# untitled.net
KiCad netlist of a schematic drawn in EAGLE
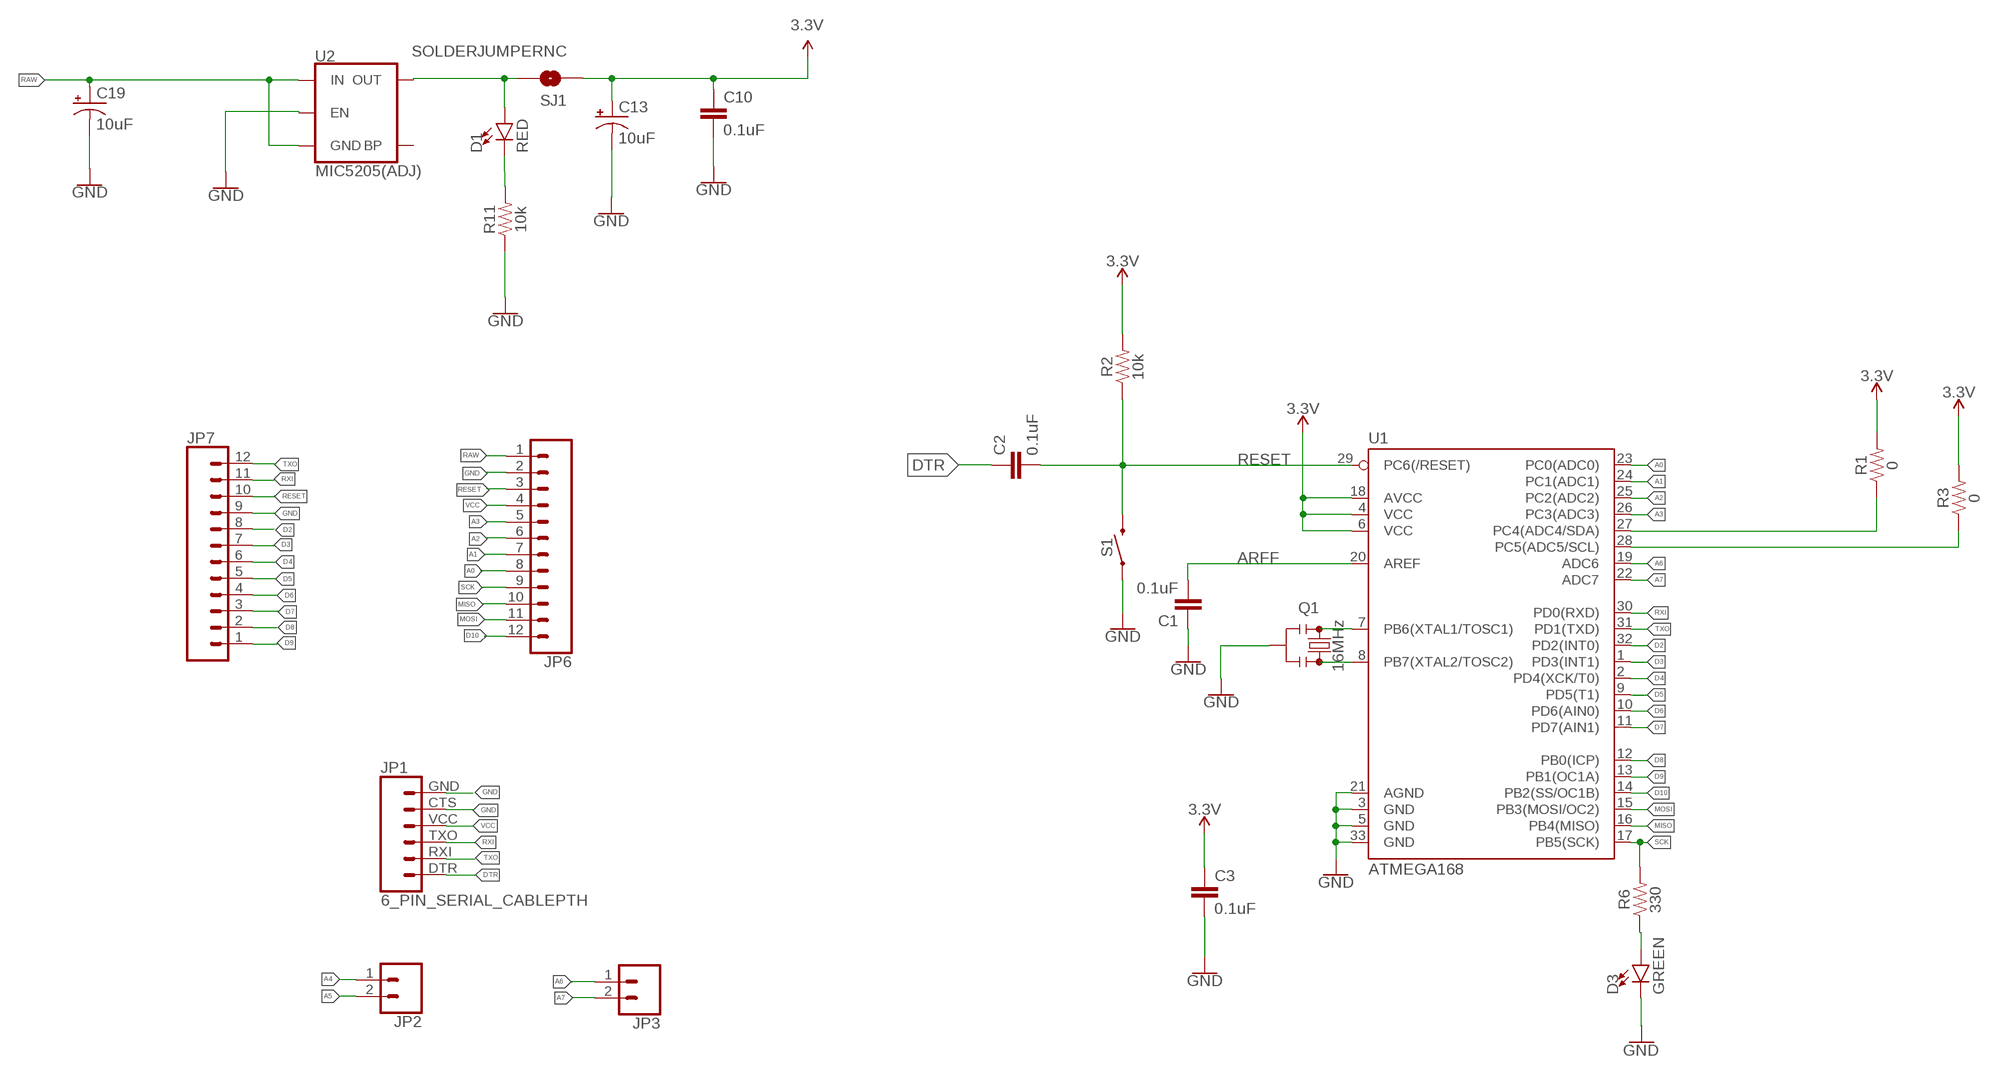
[diagram p0: schematic, sheet 1]

(export (version "E")
  (design (tool "Eeschema 10.0.6"))
  (components
    (comp (ref "C1")
      (value "0.1uF")
      (footprint "eagle-import:0603")
      (libsource (lib "eagle-import") (part "0.1UF-0603-25V-(+80/-20%)"))
    )
    (comp (ref "C2")
      (value "0.1uF")
      (footprint "eagle-import:0603")
      (libsource (lib "eagle-import") (part "0.1UF-0603-25V-(+80/-20%)"))
    )
    (comp (ref "C3")
      (value "0.1uF")
      (footprint "eagle-import:0603")
      (libsource (lib "eagle-import") (part "0.1UF-0603-25V-(+80/-20%)"))
    )
    (comp (ref "C10")
      (value "0.1uF")
      (footprint "eagle-import:0603")
      (libsource (lib "eagle-import") (part "0.1UF-0603-25V-(+80/-20%)"))
    )
    (comp (ref "C13")
      (value "10uF")
      (footprint "eagle-import:0603-POLAR")
      (libsource (lib "eagle-import") (part "10UF-POLAR-0603-6.3V-20%(TANT)"))
    )
    (comp (ref "C19")
      (value "10uF")
      (footprint "eagle-import:0603-POLAR")
      (libsource (lib "eagle-import") (part "10UF-POLAR-0603-6.3V-20%(TANT)"))
    )
    (comp (ref "D1")
      (value "RED")
      (footprint "eagle-import:LED-0603")
      (libsource (lib "eagle-import") (part "LED-RED0603"))
    )
    (comp (ref "D3")
      (value "GREEN")
      (footprint "eagle-import:LED-0603")
      (libsource (lib "eagle-import") (part "LED-GREEN0603"))
    )
    (comp (ref "JP1")
      (value "6_PIN_SERIAL_CABLEPTH")
      (footprint "eagle-import:FTDI_BASIC")
      (libsource (lib "eagle-import") (part "6_PIN_SERIAL_CABLEPTH"))
    )
    (comp (ref "JP2")
      (value "CONN_02")
      (footprint "eagle-import:1X02")
      (libsource (lib "eagle-import") (part "CONN_02"))
    )
    (comp (ref "JP3")
      (value "CONN_02")
      (footprint "eagle-import:1X02")
      (libsource (lib "eagle-import") (part "CONN_02"))
    )
    (comp (ref "JP6")
      (value "CONN_12")
      (footprint "eagle-import:1X12")
      (libsource (lib "eagle-import") (part "CONN_12"))
    )
    (comp (ref "JP7")
      (value "CONN_12")
      (footprint "eagle-import:1X12")
      (libsource (lib "eagle-import") (part "CONN_12"))
    )
    (comp (ref "Q1")
      (value "16MHz")
      (footprint "eagle-import:RESONATOR-SMD-3.2X1.3")
      (libsource (lib "eagle-import") (part "RESONATOR-16MHZSMD_3.2X1.3"))
    )
    (comp (ref "R1")
      (value "0")
      (footprint "eagle-import:0603")
      (libsource (lib "eagle-import") (part "0OHM-0603-1/10W"))
    )
    (comp (ref "R2")
      (value "10k")
      (footprint "eagle-import:0603")
      (libsource (lib "eagle-import") (part "10KOHM-0603-1/10W-1%"))
    )
    (comp (ref "R3")
      (value "0")
      (footprint "eagle-import:0603")
      (libsource (lib "eagle-import") (part "0OHM-0603-1/10W"))
    )
    (comp (ref "R6")
      (value "330")
      (footprint "eagle-import:0603")
      (libsource (lib "eagle-import") (part "330OHM-0603-1/10W-1%"))
    )
    (comp (ref "R11")
      (value "10k")
      (footprint "eagle-import:0603")
      (libsource (lib "eagle-import") (part "10KOHM-0603-1/10W-1%"))
    )
    (comp (ref "S1")
      (value "MOMENTARY-SWITCH-SPST-SMD-5.2-TALL-REDUNDANT")
      (footprint "eagle-import:TACTILE_SWITCH_SMD_5.2MM")
      (libsource (lib "eagle-import") (part "MOMENTARY-SWITCH-SPST-SMD-5.2-TALL-REDUNDANT"))
    )
    (comp (ref "SJ1")
      (value "SOLDERJUMPERNC")
      (footprint "eagle-import:SJ_2S")
      (libsource (lib "eagle-import") (part "SOLDERJUMPERNC"))
    )
    (comp (ref "U1")
      (value "ATMEGA168")
      (footprint "eagle-import:MLF32")
      (libsource (lib "eagle-import") (part "ATMEGA168_MLFMLF"))
    )
    (comp (ref "U2")
      (value "MIC5205(ADJ)")
      (footprint "eagle-import:SOT23-5")
      (libsource (lib "eagle-import") (part "V_REG_MIC5205ADJ"))
    )
  )
  (nets
    (net (code "1") (name "/ARFF") (class "Default")
      (node (ref "C1") (pin "2") (pinfunction "2_2") (pintype "passive"))
      (node (ref "U1") (pin "20") (pinfunction "AREF_20") (pintype "bidirectional"))
    )
    (net (code "2") (name "3.3V") (class "Default")
      (node (ref "C10") (pin "1") (pinfunction "1_1") (pintype "passive"))
      (node (ref "C13") (pin "+") (pinfunction "+_+") (pintype "passive"))
      (node (ref "C3") (pin "1") (pinfunction "1_1") (pintype "passive"))
      (node (ref "R1") (pin "2") (pinfunction "2_2") (pintype "passive"))
      (node (ref "R2") (pin "2") (pinfunction "2_2") (pintype "passive"))
      (node (ref "R3") (pin "2") (pinfunction "2_2") (pintype "passive"))
      (node (ref "SJ1") (pin "1") (pinfunction "1_1") (pintype "passive"))
      (node (ref "U1") (pin "18") (pinfunction "AVCC_18") (pintype "bidirectional"))
      (node (ref "U1") (pin "4") (pinfunction "VCC_4") (pintype "bidirectional"))
      (node (ref "U1") (pin "6") (pinfunction "VCC_6") (pintype "bidirectional"))
    )
    (net (code "3") (name "A0") (class "Default")
      (node (ref "JP6") (pin "8") (pinfunction "8_8") (pintype "passive"))
      (node (ref "U1") (pin "23") (pinfunction "PC0(ADC0)_23") (pintype "bidirectional"))
    )
    (net (code "4") (name "A1") (class "Default")
      (node (ref "JP6") (pin "7") (pinfunction "7_7") (pintype "passive"))
      (node (ref "U1") (pin "24") (pinfunction "PC1(ADC1)_24") (pintype "bidirectional"))
    )
    (net (code "5") (name "A2") (class "Default")
      (node (ref "JP6") (pin "6") (pinfunction "6_6") (pintype "passive"))
      (node (ref "U1") (pin "25") (pinfunction "PC2(ADC2)_25") (pintype "bidirectional"))
    )
    (net (code "6") (name "A3") (class "Default")
      (node (ref "JP6") (pin "5") (pinfunction "5_5") (pintype "passive"))
      (node (ref "U1") (pin "26") (pinfunction "PC3(ADC3)_26") (pintype "bidirectional"))
    )
    (net (code "7") (name "A4") (class "Default")
      (node (ref "JP2") (pin "1") (pinfunction "1_1") (pintype "passive"))
    )
    (net (code "8") (name "A5") (class "Default")
      (node (ref "JP2") (pin "2") (pinfunction "2_2") (pintype "passive"))
    )
    (net (code "9") (name "A6") (class "Default")
      (node (ref "JP3") (pin "1") (pinfunction "1_1") (pintype "passive"))
      (node (ref "U1") (pin "19") (pinfunction "ADC6_19") (pintype "bidirectional"))
    )
    (net (code "10") (name "A7") (class "Default")
      (node (ref "JP3") (pin "2") (pinfunction "2_2") (pintype "passive"))
      (node (ref "U1") (pin "22") (pinfunction "ADC7_22") (pintype "bidirectional"))
    )
    (net (code "11") (name "D2") (class "Default")
      (node (ref "JP7") (pin "8") (pinfunction "8_8") (pintype "passive"))
      (node (ref "U1") (pin "32") (pinfunction "PD2(INT0)_32") (pintype "bidirectional"))
    )
    (net (code "12") (name "D3") (class "Default")
      (node (ref "JP7") (pin "7") (pinfunction "7_7") (pintype "passive"))
      (node (ref "U1") (pin "1") (pinfunction "PD3(INT1)_1") (pintype "bidirectional"))
    )
    (net (code "13") (name "D4") (class "Default")
      (node (ref "JP7") (pin "6") (pinfunction "6_6") (pintype "passive"))
      (node (ref "U1") (pin "2") (pinfunction "PD4(XCK/T0)_2") (pintype "bidirectional"))
    )
    (net (code "14") (name "D5") (class "Default")
      (node (ref "JP7") (pin "5") (pinfunction "5_5") (pintype "passive"))
      (node (ref "U1") (pin "9") (pinfunction "PD5(T1)_9") (pintype "bidirectional"))
    )
    (net (code "15") (name "D6") (class "Default")
      (node (ref "JP7") (pin "4") (pinfunction "4_4") (pintype "passive"))
      (node (ref "U1") (pin "10") (pinfunction "PD6(AIN0)_10") (pintype "bidirectional"))
    )
    (net (code "16") (name "D7") (class "Default")
      (node (ref "JP7") (pin "3") (pinfunction "3_3") (pintype "passive"))
      (node (ref "U1") (pin "11") (pinfunction "PD7(AIN1)_11") (pintype "bidirectional"))
    )
    (net (code "17") (name "D8") (class "Default")
      (node (ref "JP7") (pin "2") (pinfunction "2_2") (pintype "passive"))
      (node (ref "U1") (pin "12") (pinfunction "PB0(ICP)_12") (pintype "bidirectional"))
    )
    (net (code "18") (name "D9") (class "Default")
      (node (ref "JP7") (pin "1") (pinfunction "1_1") (pintype "passive"))
      (node (ref "U1") (pin "13") (pinfunction "PB1(OC1A)_13") (pintype "bidirectional"))
    )
    (net (code "19") (name "D10") (class "Default")
      (node (ref "JP6") (pin "12") (pinfunction "12_12") (pintype "passive"))
      (node (ref "U1") (pin "14") (pinfunction "PB2(SS/OC1B)_14") (pintype "bidirectional"))
    )
    (net (code "20") (name "DTR") (class "Default")
      (node (ref "C2") (pin "1") (pinfunction "1_1") (pintype "passive"))
      (node (ref "JP1") (pin "DTR") (pinfunction "1_DTR") (pintype "passive"))
    )
    (net (code "21") (name "GND") (class "Default")
      (node (ref "C1") (pin "1") (pinfunction "1_1") (pintype "passive"))
      (node (ref "C10") (pin "2") (pinfunction "2_2") (pintype "passive"))
      (node (ref "C13") (pin "-") (pinfunction "-_-") (pintype "passive"))
      (node (ref "C19") (pin "-") (pinfunction "-_-") (pintype "passive"))
      (node (ref "C3") (pin "2") (pinfunction "2_2") (pintype "passive"))
      (node (ref "D3") (pin "C") (pinfunction "C_C") (pintype "passive"))
      (node (ref "JP1") (pin "CTS") (pinfunction "5_CTS") (pintype "passive"))
      (node (ref "JP1") (pin "GND") (pinfunction "6_GND") (pintype "passive"))
      (node (ref "JP6") (pin "2") (pinfunction "2_2") (pintype "passive"))
      (node (ref "JP7") (pin "9") (pinfunction "9_9") (pintype "passive"))
      (node (ref "Q1") (pin "2") (pinfunction "2_2") (pintype "passive"))
      (node (ref "R11") (pin "1") (pinfunction "1_1") (pintype "passive"))
      (node (ref "S1") (pin "1") (pinfunction "1_1") (pintype "passive"))
      (node (ref "S1") (pin "2") (pinfunction "1_2") (pintype "passive"))
      (node (ref "U1") (pin "21") (pinfunction "AGND_21") (pintype "bidirectional"))
      (node (ref "U1") (pin "3") (pinfunction "GND_3") (pintype "bidirectional"))
      (node (ref "U1") (pin "33") (pinfunction "GND_33") (pintype "bidirectional"))
      (node (ref "U1") (pin "5") (pinfunction "GND_5") (pintype "bidirectional"))
      (node (ref "U2") (pin "3") (pinfunction "EN_3") (pintype "input"))
    )
    (net (code "22") (name "MISO") (class "Default")
      (node (ref "JP6") (pin "10") (pinfunction "10_10") (pintype "passive"))
      (node (ref "U1") (pin "16") (pinfunction "PB4(MISO)_16") (pintype "bidirectional"))
    )
    (net (code "23") (name "MOSI") (class "Default")
      (node (ref "JP6") (pin "11") (pinfunction "11_11") (pintype "passive"))
      (node (ref "U1") (pin "15") (pinfunction "PB3(MOSI/OC2)_15") (pintype "bidirectional"))
    )
    (net (code "24") (name "Net-(D1-PadC)") (class "Default")
      (node (ref "D1") (pin "C") (pinfunction "C_C") (pintype "passive"))
      (node (ref "R11") (pin "2") (pinfunction "2_2") (pintype "passive"))
    )
    (net (code "25") (name "Net-(D3-PadA)") (class "Default")
      (node (ref "D3") (pin "A") (pinfunction "A_A") (pintype "passive"))
      (node (ref "R6") (pin "1") (pinfunction "1_1") (pintype "passive"))
    )
    (net (code "26") (name "Net-(U1-PB6(XTAL1{slash}TOSC1))") (class "Default")
      (node (ref "Q1") (pin "1") (pinfunction "1_1") (pintype "passive"))
      (node (ref "U1") (pin "7") (pinfunction "PB6(XTAL1/TOSC1)_7") (pintype "bidirectional"))
    )
    (net (code "27") (name "Net-(U1-PB7(XTAL2{slash}TOSC2))") (class "Default")
      (node (ref "Q1") (pin "3") (pinfunction "3_3") (pintype "passive"))
      (node (ref "U1") (pin "8") (pinfunction "PB7(XTAL2/TOSC2)_8") (pintype "bidirectional"))
    )
    (net (code "28") (name "Net-(U1-PC4(ADC4{slash}SDA))") (class "Default")
      (node (ref "R1") (pin "1") (pinfunction "1_1") (pintype "passive"))
      (node (ref "U1") (pin "27") (pinfunction "PC4(ADC4/SDA)_27") (pintype "bidirectional"))
    )
    (net (code "29") (name "Net-(U1-PC5(ADC5{slash}SCL))") (class "Default")
      (node (ref "R3") (pin "1") (pinfunction "1_1") (pintype "passive"))
      (node (ref "U1") (pin "28") (pinfunction "PC5(ADC5/SCL)_28") (pintype "bidirectional"))
    )
    (net (code "30") (name "Net-(U2-OUT)") (class "Default")
      (node (ref "D1") (pin "A") (pinfunction "A_A") (pintype "passive"))
      (node (ref "SJ1") (pin "2") (pinfunction "2_2") (pintype "passive"))
      (node (ref "U2") (pin "5") (pinfunction "OUT_5") (pintype "passive"))
    )
    (net (code "31") (name "RAW") (class "Default")
      (node (ref "C19") (pin "+") (pinfunction "+_+") (pintype "passive"))
      (node (ref "JP6") (pin "1") (pinfunction "1_1") (pintype "passive"))
      (node (ref "U2") (pin "1") (pinfunction "IN_1") (pintype "input"))
      (node (ref "U2") (pin "2") (pinfunction "GND_2") (pintype "input"))
    )
    (net (code "32") (name "RESET") (class "Default")
      (node (ref "C2") (pin "2") (pinfunction "2_2") (pintype "passive"))
      (node (ref "JP6") (pin "3") (pinfunction "3_3") (pintype "passive"))
      (node (ref "JP7") (pin "10") (pinfunction "10_10") (pintype "passive"))
      (node (ref "R2") (pin "1") (pinfunction "1_1") (pintype "passive"))
      (node (ref "S1") (pin "3") (pinfunction "2_3") (pintype "passive"))
      (node (ref "S1") (pin "4") (pinfunction "2_4") (pintype "passive"))
      (node (ref "U1") (pin "29") (pinfunction "PC6(/RESET)_29") (pintype "bidirectional"))
    )
    (net (code "33") (name "RXI") (class "Default")
      (node (ref "JP1") (pin "TXO") (pinfunction "3_TXO") (pintype "passive"))
      (node (ref "JP7") (pin "11") (pinfunction "11_11") (pintype "passive"))
      (node (ref "U1") (pin "30") (pinfunction "PD0(RXD)_30") (pintype "bidirectional"))
    )
    (net (code "34") (name "SCK") (class "Default")
      (node (ref "JP6") (pin "9") (pinfunction "9_9") (pintype "passive"))
      (node (ref "R6") (pin "2") (pinfunction "2_2") (pintype "passive"))
      (node (ref "U1") (pin "17") (pinfunction "PB5(SCK)_17") (pintype "bidirectional"))
    )
    (net (code "35") (name "TXO") (class "Default")
      (node (ref "JP1") (pin "RXI") (pinfunction "2_RXI") (pintype "passive"))
      (node (ref "JP7") (pin "12") (pinfunction "12_12") (pintype "passive"))
      (node (ref "U1") (pin "31") (pinfunction "PD1(TXD)_31") (pintype "bidirectional"))
    )
    (net (code "36") (name "VCC") (class "Default")
      (node (ref "JP1") (pin "VCC") (pinfunction "4_VCC") (pintype "passive"))
      (node (ref "JP6") (pin "4") (pinfunction "4_4") (pintype "passive"))
    )
    (net (code "37") (name "unconnected-(U2-BP-Pad4)") (class "Default")
      (node (ref "U2") (pin "4") (pinfunction "BP_4") (pintype "input"))
    )
  )
)
